# Argo2_Receiver.net
KiCad netlist of a schematic drawn in EAGLE
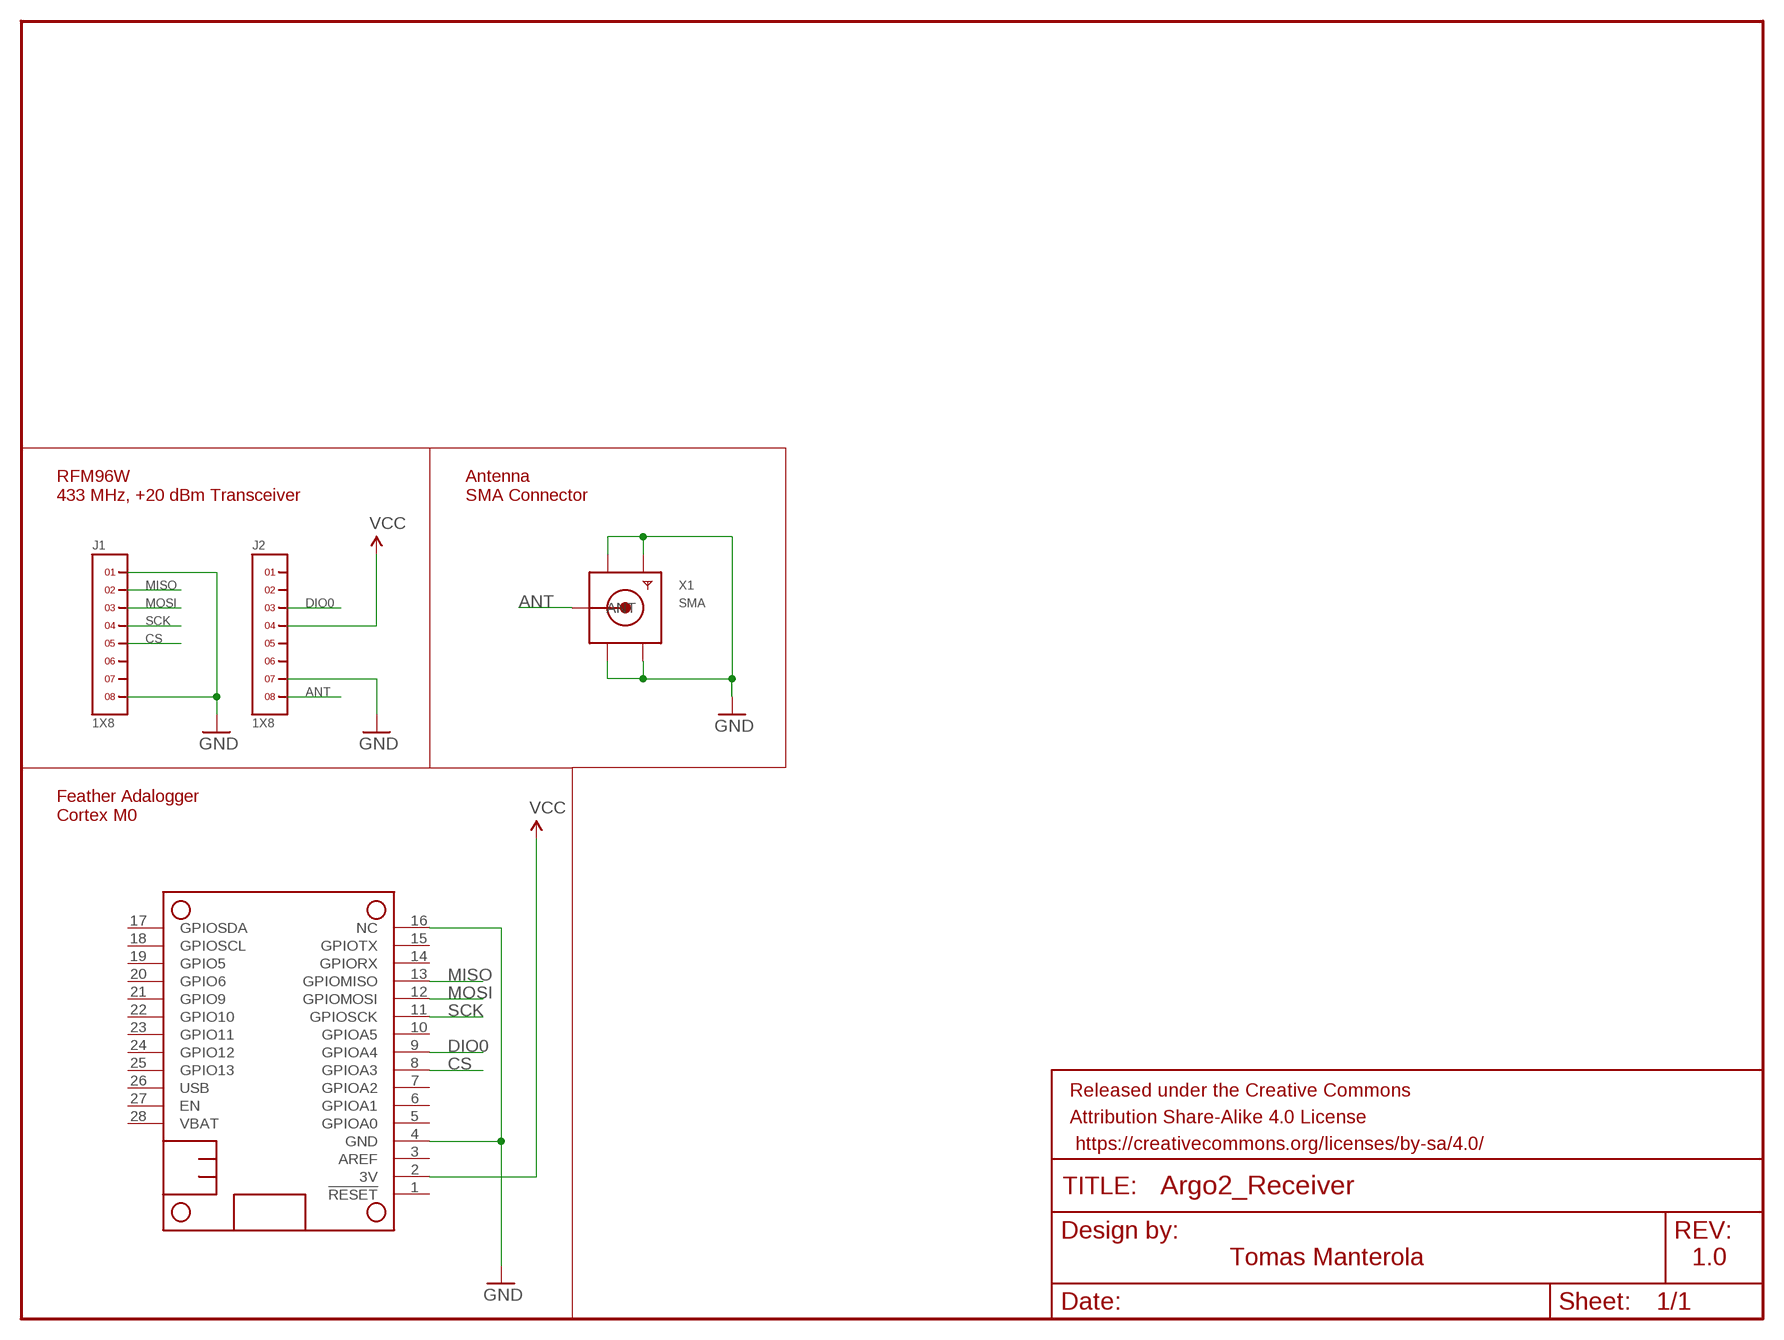
[diagram p0: schematic, sheet 1]

(export (version "E")
  (design (tool "Eeschema 10.0.6"))
  (components
    (comp (ref "FRAME1")
      (value "FRAME-LETTERNO_PACKAGE")
      (footprint "eagle-import:DUMMY")
      (fields (field (name "DESIGNER") "Tomas Manterola") (field (name "VERSION") "1.0"))
      (libsource (lib "eagle-import") (part "FRAME-LETTERNO_PACKAGE"))
    )
    (comp (ref "J1")
      (value "1X8")
      (footprint "eagle-import:1X8")
      (libsource (lib "eagle-import") (part "1X8"))
    )
    (comp (ref "J2")
      (value "1X8")
      (footprint "eagle-import:1X8")
      (libsource (lib "eagle-import") (part "1X8"))
    )
    (comp (ref "MS1")
      (value "FEATHERWING_NODIM")
      (footprint "eagle-import:FEATHERWING_DIM")
      (libsource (lib "eagle-import") (part "FEATHERWING_NODIM"))
    )
    (comp (ref "X1")
      (value "SMA")
      (footprint "eagle-import:SMA_EDGELAUNCH")
      (libsource (lib "eagle-import") (part "SMACONNECTOR_EDGE"))
    )
  )
  (nets
    (net (code "1") (name "/ANT") (class "Default")
      (node (ref "J2") (pin "8") (pinfunction "8_8") (pintype "bidirectional"))
      (node (ref "X1") (pin "P") (pinfunction "ANT_P") (pintype "bidirectional"))
    )
    (net (code "2") (name "/CS") (class "Default")
      (node (ref "J1") (pin "5") (pinfunction "5_5") (pintype "bidirectional"))
      (node (ref "MS1") (pin "8") (pinfunction "GPIOA3_8") (pintype "bidirectional"))
    )
    (net (code "3") (name "/DIO0") (class "Default")
      (node (ref "J2") (pin "3") (pinfunction "3_3") (pintype "bidirectional"))
      (node (ref "MS1") (pin "9") (pinfunction "GPIOA4_9") (pintype "bidirectional"))
    )
    (net (code "4") (name "/MISO") (class "Default")
      (node (ref "J1") (pin "2") (pinfunction "2_2") (pintype "bidirectional"))
      (node (ref "MS1") (pin "13") (pinfunction "GPIOMISO_13") (pintype "bidirectional"))
    )
    (net (code "5") (name "/MOSI") (class "Default")
      (node (ref "J1") (pin "3") (pinfunction "3_3") (pintype "bidirectional"))
      (node (ref "MS1") (pin "12") (pinfunction "GPIOMOSI_12") (pintype "bidirectional"))
    )
    (net (code "6") (name "/SCK") (class "Default")
      (node (ref "J1") (pin "4") (pinfunction "4_4") (pintype "bidirectional"))
      (node (ref "MS1") (pin "11") (pinfunction "GPIOSCK_11") (pintype "bidirectional"))
    )
    (net (code "7") (name "/USB") (class "Default")
      (node (ref "MS1") (pin "26") (pinfunction "USB_26") (pintype "power_in"))
    )
    (net (code "8") (name "/VBAT") (class "Default")
      (node (ref "MS1") (pin "28") (pinfunction "VBAT_28") (pintype "power_in"))
    )
    (net (code "9") (name "GND") (class "Default")
      (node (ref "J1") (pin "1") (pinfunction "1_1") (pintype "bidirectional"))
      (node (ref "J1") (pin "8") (pinfunction "8_8") (pintype "bidirectional"))
      (node (ref "J2") (pin "7") (pinfunction "7_7") (pintype "bidirectional"))
      (node (ref "MS1") (pin "16") (pinfunction "NC_16") (pintype "passive"))
      (node (ref "MS1") (pin "4") (pinfunction "GND_4") (pintype "power_in"))
      (node (ref "X1") (pin "GND@1") (pinfunction "GND4_GND@1") (pintype "power_in"))
      (node (ref "X1") (pin "GND@2") (pinfunction "GND3_GND@2") (pintype "power_in"))
      (node (ref "X1") (pin "GND@3") (pinfunction "GND2_GND@3") (pintype "power_in"))
      (node (ref "X1") (pin "GND@4") (pinfunction "GND1_GND@4") (pintype "power_in"))
    )
    (net (code "10") (name "VCC") (class "Default")
      (node (ref "J2") (pin "4") (pinfunction "4_4") (pintype "bidirectional"))
      (node (ref "MS1") (pin "2") (pinfunction "3V_2") (pintype "power_in"))
    )
    (net (code "11") (name "unconnected-(J1-Pad6)") (class "Default")
      (node (ref "J1") (pin "6") (pinfunction "6_6") (pintype "bidirectional"))
    )
    (net (code "12") (name "unconnected-(J1-Pad7)") (class "Default")
      (node (ref "J1") (pin "7") (pinfunction "7_7") (pintype "bidirectional"))
    )
    (net (code "13") (name "unconnected-(J2-Pad1)") (class "Default")
      (node (ref "J2") (pin "1") (pinfunction "1_1") (pintype "bidirectional"))
    )
    (net (code "14") (name "unconnected-(J2-Pad2)") (class "Default")
      (node (ref "J2") (pin "2") (pinfunction "2_2") (pintype "bidirectional"))
    )
    (net (code "15") (name "unconnected-(J2-Pad5)") (class "Default")
      (node (ref "J2") (pin "5") (pinfunction "5_5") (pintype "bidirectional"))
    )
    (net (code "16") (name "unconnected-(J2-Pad6)") (class "Default")
      (node (ref "J2") (pin "6") (pinfunction "6_6") (pintype "bidirectional"))
    )
    (net (code "17") (name "unconnected-(MS1-AREF-Pad3)") (class "Default")
      (node (ref "MS1") (pin "3") (pinfunction "AREF_3") (pintype "passive"))
    )
    (net (code "18") (name "unconnected-(MS1-EN-Pad27)") (class "Default")
      (node (ref "MS1") (pin "27") (pinfunction "EN_27") (pintype "passive"))
    )
    (net (code "19") (name "unconnected-(MS1-GPIO5-Pad19)") (class "Default")
      (node (ref "MS1") (pin "19") (pinfunction "GPIO5_19") (pintype "bidirectional"))
    )
    (net (code "20") (name "unconnected-(MS1-GPIO6-Pad20)") (class "Default")
      (node (ref "MS1") (pin "20") (pinfunction "GPIO6_20") (pintype "bidirectional"))
    )
    (net (code "21") (name "unconnected-(MS1-GPIO9-Pad21)") (class "Default")
      (node (ref "MS1") (pin "21") (pinfunction "GPIO9_21") (pintype "bidirectional"))
    )
    (net (code "22") (name "unconnected-(MS1-GPIO10-Pad22)") (class "Default")
      (node (ref "MS1") (pin "22") (pinfunction "GPIO10_22") (pintype "bidirectional"))
    )
    (net (code "23") (name "unconnected-(MS1-GPIO11-Pad23)") (class "Default")
      (node (ref "MS1") (pin "23") (pinfunction "GPIO11_23") (pintype "bidirectional"))
    )
    (net (code "24") (name "unconnected-(MS1-GPIO12-Pad24)") (class "Default")
      (node (ref "MS1") (pin "24") (pinfunction "GPIO12_24") (pintype "bidirectional"))
    )
    (net (code "25") (name "unconnected-(MS1-GPIO13-Pad25)") (class "Default")
      (node (ref "MS1") (pin "25") (pinfunction "GPIO13_25") (pintype "bidirectional"))
    )
    (net (code "26") (name "unconnected-(MS1-GPIOA0-Pad5)") (class "Default")
      (node (ref "MS1") (pin "5") (pinfunction "GPIOA0_5") (pintype "bidirectional"))
    )
    (net (code "27") (name "unconnected-(MS1-GPIOA1-Pad6)") (class "Default")
      (node (ref "MS1") (pin "6") (pinfunction "GPIOA1_6") (pintype "bidirectional"))
    )
    (net (code "28") (name "unconnected-(MS1-GPIOA2-Pad7)") (class "Default")
      (node (ref "MS1") (pin "7") (pinfunction "GPIOA2_7") (pintype "bidirectional"))
    )
    (net (code "29") (name "unconnected-(MS1-GPIOA5-Pad10)") (class "Default")
      (node (ref "MS1") (pin "10") (pinfunction "GPIOA5_10") (pintype "bidirectional"))
    )
    (net (code "30") (name "unconnected-(MS1-GPIORX-Pad14)") (class "Default")
      (node (ref "MS1") (pin "14") (pinfunction "GPIORX_14") (pintype "bidirectional"))
    )
    (net (code "31") (name "unconnected-(MS1-GPIOSCL-Pad18)") (class "Default")
      (node (ref "MS1") (pin "18") (pinfunction "GPIOSCL_18") (pintype "bidirectional"))
    )
    (net (code "32") (name "unconnected-(MS1-GPIOSDA-Pad17)") (class "Default")
      (node (ref "MS1") (pin "17") (pinfunction "GPIOSDA_17") (pintype "bidirectional"))
    )
    (net (code "33") (name "unconnected-(MS1-GPIOTX-Pad15)") (class "Default")
      (node (ref "MS1") (pin "15") (pinfunction "GPIOTX_15") (pintype "bidirectional"))
    )
    (net (code "34") (name "unconnected-(MS1-~{RESET}-Pad1)") (class "Default")
      (node (ref "MS1") (pin "1") (pinfunction "~{RESET}_1") (pintype "input"))
    )
  )
)
